# gy1.net
KiCad netlist of a schematic drawn in EAGLE
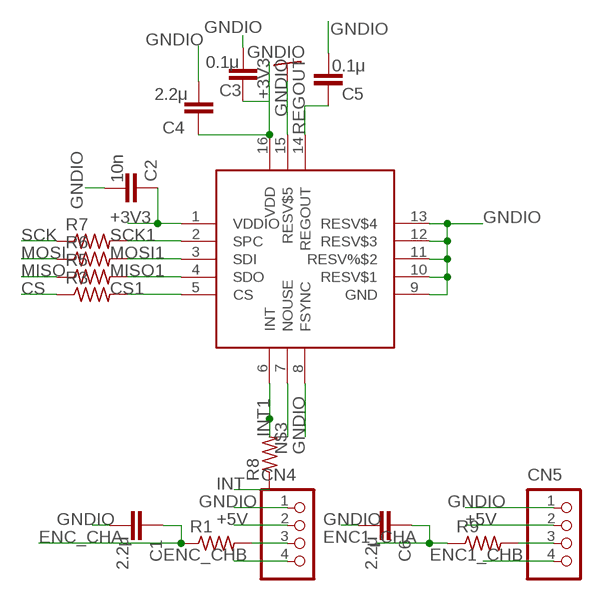
[diagram p0: schematic, sheet 1]
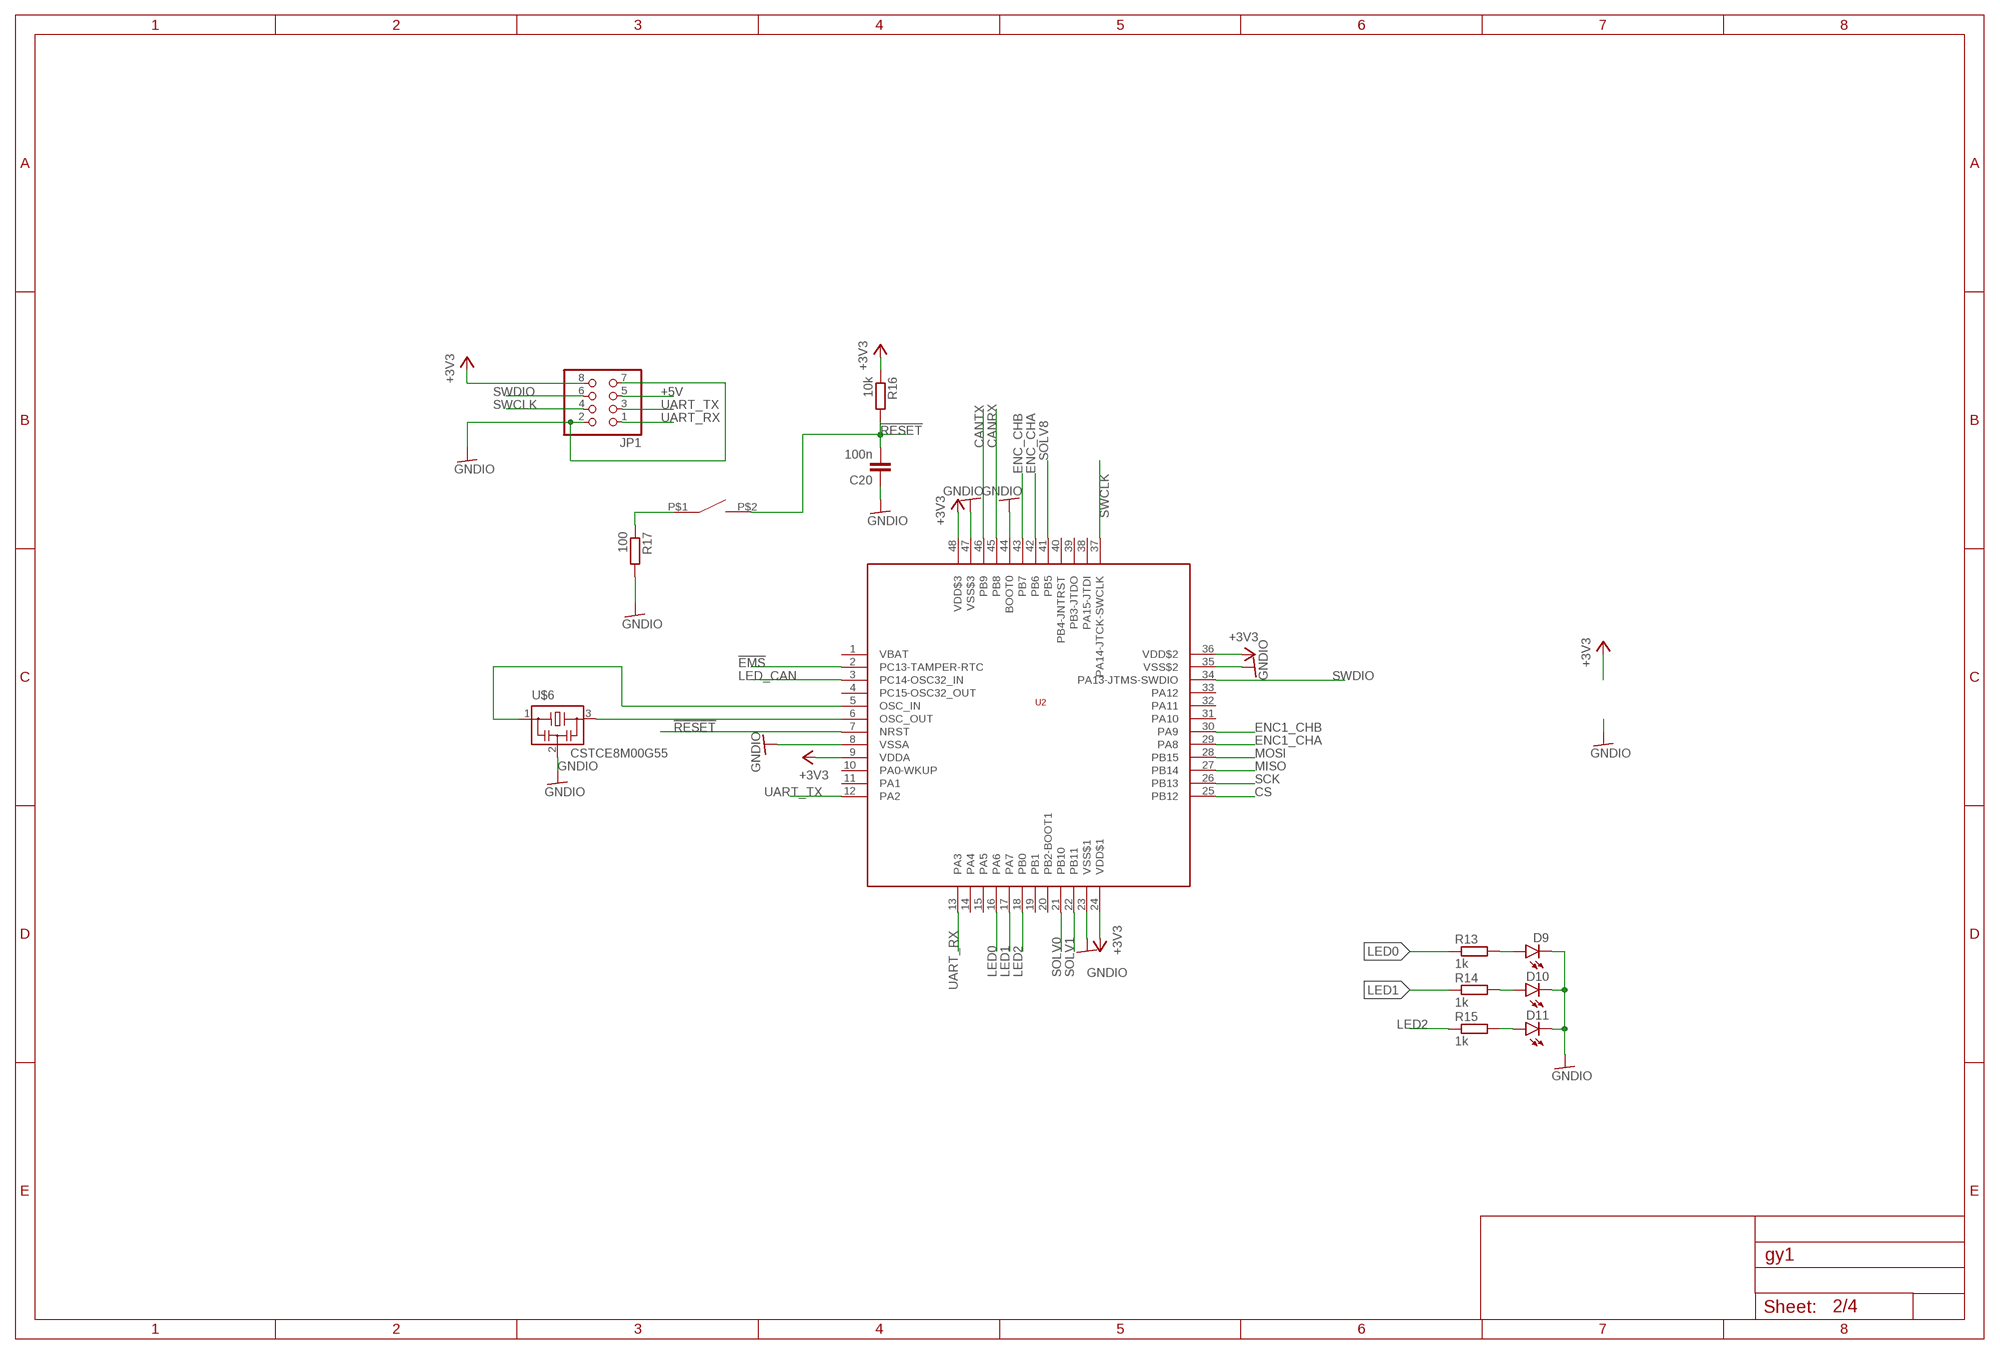
[diagram p1: schematic, sheet 2]
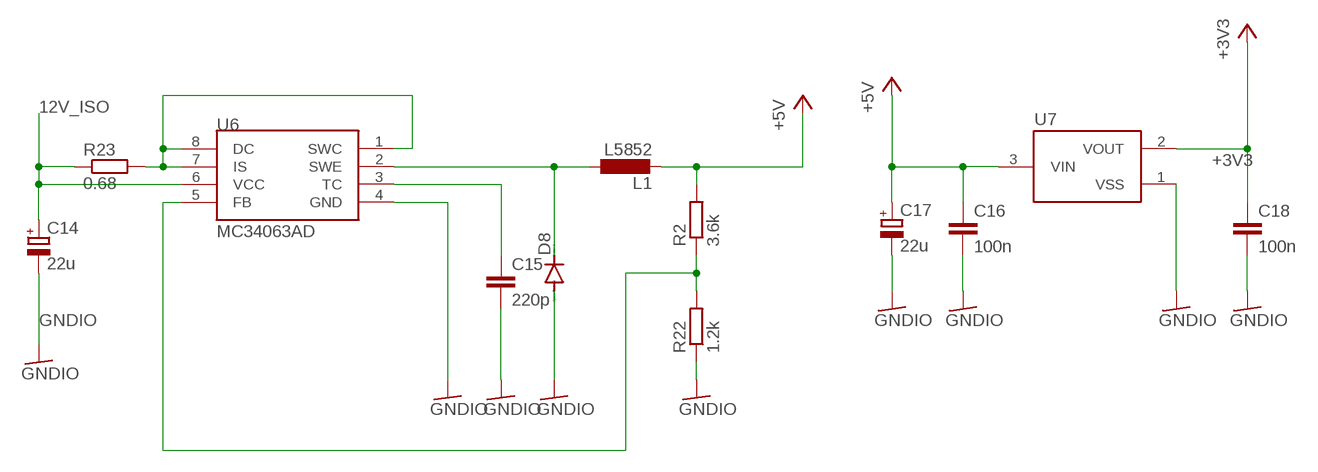
[diagram p2: schematic, sheet 3]
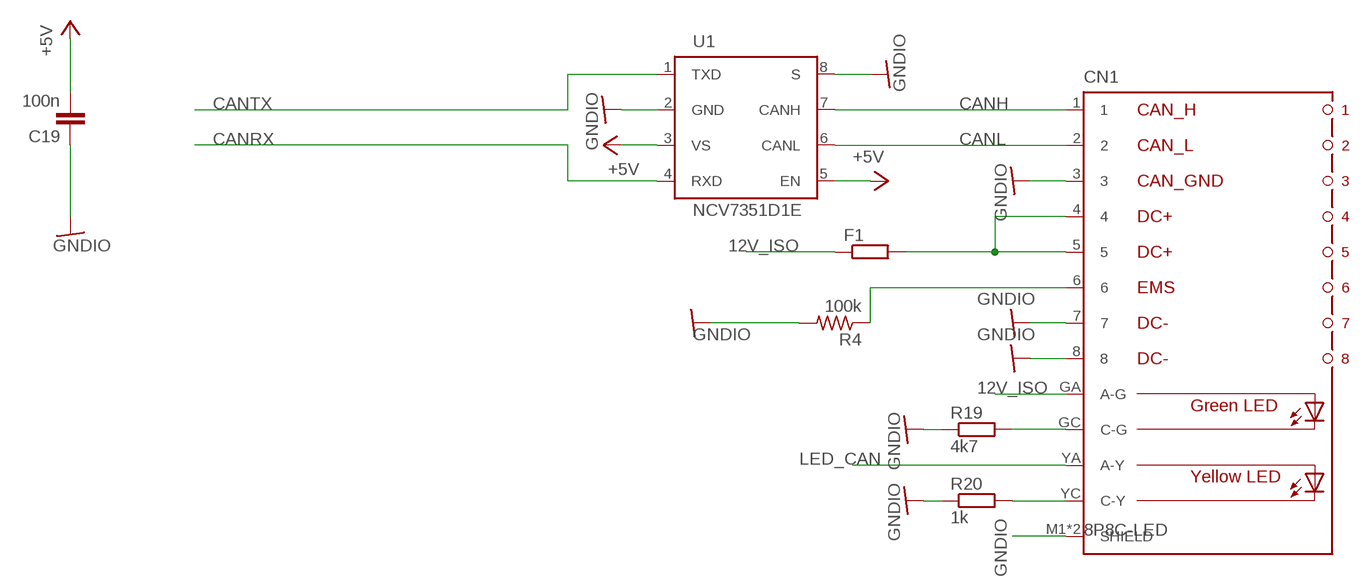
[diagram p3: schematic, sheet 4]

(export (version "E")
  (design (tool "Eeschema 10.0.6"))
  (components
    (comp (ref "C14")
      (value "22u")
      (footprint "eagle-import:E2-5")
      (libsource (lib "eagle-import") (part "CPOL-EUE2-5"))
    )
    (comp (ref "C15")
      (value "220p")
      (footprint "eagle-import:C0603")
      (libsource (lib "eagle-import") (part "rcl_334_C-EUC0603"))
    )
    (comp (ref "C16")
      (value "100n")
      (footprint "eagle-import:C0603")
      (libsource (lib "eagle-import") (part "C-EUC0603"))
    )
    (comp (ref "C17")
      (value "22u")
      (footprint "eagle-import:E2-5")
      (libsource (lib "eagle-import") (part "CPOL-EUE2-5"))
    )
    (comp (ref "C18")
      (value "100n")
      (footprint "eagle-import:C0603")
      (libsource (lib "eagle-import") (part "C-EUC0603"))
    )
    (comp (ref "D8")
      (value "DIODE-SOD123")
      (footprint "eagle-import:SOD123")
      (libsource (lib "eagle-import") (part "DIODE-SOD123"))
    )
    (comp (ref "L1")
      (value "L5852")
      (footprint "eagle-import:L5852")
      (libsource (lib "eagle-import") (part "L5852"))
    )
    (comp (ref "R2")
      (value "3.6k")
      (footprint "eagle-import:R0603")
      (libsource (lib "eagle-import") (part "rcl_334_R-EU_R0603"))
    )
    (comp (ref "R22")
      (value "1.2k")
      (footprint "eagle-import:R0603")
      (libsource (lib "eagle-import") (part "rcl_334_R-EU_R0603"))
    )
    (comp (ref "R23")
      (value "0.68")
      (footprint "eagle-import:R1206")
      (libsource (lib "eagle-import") (part "rcl_334_R-EU_R1206"))
    )
    (comp (ref "U6")
      (value "MC34063AD")
      (footprint "eagle-import:SOIC8")
      (libsource (lib "eagle-import") (part "MC34063AD"))
    )
    (comp (ref "U7")
      (value "XC6206")
      (footprint "eagle-import:SOT95P240X110-3")
      (libsource (lib "eagle-import") (part "XC6206"))
    )
    (comp (ref "C19")
      (value "100n")
      (footprint "eagle-import:C0603")
      (libsource (lib "eagle-import") (part "C-EUC0603"))
    )
    (comp (ref "CN1")
      (value "8P8C-LED")
      (footprint "eagle-import:8P8C-LED")
      (libsource (lib "eagle-import") (part "8P8C-LED"))
    )
    (comp (ref "F1")
      (value "R-EU_R1206")
      (footprint "eagle-import:R1206")
      (libsource (lib "eagle-import") (part "rcl_334_R-EU_R1206"))
    )
    (comp (ref "R4")
      (value "100k")
      (footprint "eagle-import:R0603")
      (libsource (lib "eagle-import") (part "R-US_R0603"))
    )
    (comp (ref "R19")
      (value "4k7")
      (footprint "eagle-import:R0603")
      (libsource (lib "eagle-import") (part "rcl_334_R-EU_R0603"))
    )
    (comp (ref "R20")
      (value "1k")
      (footprint "eagle-import:R0603")
      (libsource (lib "eagle-import") (part "rcl_334_R-EU_R0603"))
    )
    (comp (ref "U1")
      (value "NCV7351D1E")
      (footprint "eagle-import:SO08")
      (libsource (lib "eagle-import") (part "NCV7351D1E"))
    )
    (comp (ref "C20")
      (value "100n")
      (footprint "eagle-import:C0603")
      (libsource (lib "eagle-import") (part "C-EUC0603"))
    )
    (comp (ref "D9")
      (value "LEDCHIPLED_0805")
      (footprint "eagle-import:CHIPLED_0805")
      (libsource (lib "eagle-import") (part "LEDCHIPLED_0805"))
    )
    (comp (ref "D10")
      (value "LEDCHIPLED_0805")
      (footprint "eagle-import:CHIPLED_0805")
      (libsource (lib "eagle-import") (part "LEDCHIPLED_0805"))
    )
    (comp (ref "D11")
      (value "LEDCHIPLED_0805")
      (footprint "eagle-import:CHIPLED_0805")
      (libsource (lib "eagle-import") (part "LEDCHIPLED_0805"))
    )
    (comp (ref "JP1")
      (value "PINHD-2X4")
      (footprint "eagle-import:2X04")
      (libsource (lib "eagle-import") (part "PINHD-2X4"))
    )
    (comp (ref "R13")
      (value "1k")
      (footprint "eagle-import:R0603")
      (libsource (lib "eagle-import") (part "R-EU_R0603"))
    )
    (comp (ref "R14")
      (value "1k")
      (footprint "eagle-import:R0603")
      (libsource (lib "eagle-import") (part "R-EU_R0603"))
    )
    (comp (ref "R15")
      (value "1k")
      (footprint "eagle-import:R0603")
      (libsource (lib "eagle-import") (part "R-EU_R0603"))
    )
    (comp (ref "R16")
      (value "10k")
      (footprint "eagle-import:R0603")
      (libsource (lib "eagle-import") (part "R-EU_R0603"))
    )
    (comp (ref "R17")
      (value "100")
      (footprint "eagle-import:R0603")
      (libsource (lib "eagle-import") (part "R-EU_R0603"))
    )
    (comp (ref "SW1")
      (value "SWITCH_TACTILETOP")
      (footprint "eagle-import:SWITCH_TACTILE_3X6")
      (libsource (lib "eagle-import") (part "SWITCH_TACTILETOP"))
    )
    (comp (ref "U$6")
      (value "CSTCE8M00G55")
      (footprint "eagle-import:CSTCE8M00G55")
      (libsource (lib "eagle-import") (part "CSTCE8M00G55"))
    )
    (comp (ref "U2")
      (value "STM32F103C8")
      (footprint "eagle-import:LQFP48")
      (libsource (lib "eagle-import") (part "STM32F103C8"))
    )
    (comp (ref "C1")
      (value "2.2μ")
      (footprint "eagle-import:C0603")
      (libsource (lib "eagle-import") (part "C-EUC0603"))
    )
    (comp (ref "C2")
      (value "10n")
      (footprint "eagle-import:C0603")
      (libsource (lib "eagle-import") (part "C-EUC0603"))
    )
    (comp (ref "C3")
      (value "0.1μ")
      (footprint "eagle-import:C0603")
      (libsource (lib "eagle-import") (part "C-EUC0603"))
    )
    (comp (ref "C4")
      (value "2.2μ")
      (footprint "eagle-import:C0603")
      (libsource (lib "eagle-import") (part "C-EUC0603"))
    )
    (comp (ref "C5")
      (value "0.1μ")
      (footprint "eagle-import:C0603")
      (libsource (lib "eagle-import") (part "C-EUC0603"))
    )
    (comp (ref "C6")
      (value "2.2μ")
      (footprint "eagle-import:C0603")
      (libsource (lib "eagle-import") (part "C-EUC0603"))
    )
    (comp (ref "CN4")
      (value "S4B-XASK-1")
      (footprint "eagle-import:S4B-XASK-1")
      (libsource (lib "eagle-import") (part "S4B-XASK-1"))
    )
    (comp (ref "CN5")
      (value "S4B-XASK-1")
      (footprint "eagle-import:S4B-XASK-1")
      (libsource (lib "eagle-import") (part "S4B-XASK-1"))
    )
    (comp (ref "R1")
      (value "R-US_R0603")
      (footprint "eagle-import:R0603")
      (libsource (lib "eagle-import") (part "R-US_R0603"))
    )
    (comp (ref "R3")
      (value "R-US_R0603")
      (footprint "eagle-import:R0603")
      (libsource (lib "eagle-import") (part "R-US_R0603"))
    )
    (comp (ref "R5")
      (value "R-US_R0603")
      (footprint "eagle-import:R0603")
      (libsource (lib "eagle-import") (part "R-US_R0603"))
    )
    (comp (ref "R6")
      (value "R-US_R0603")
      (footprint "eagle-import:R0603")
      (libsource (lib "eagle-import") (part "R-US_R0603"))
    )
    (comp (ref "R7")
      (value "R-US_R0603")
      (footprint "eagle-import:R0603")
      (libsource (lib "eagle-import") (part "R-US_R0603"))
    )
    (comp (ref "R8")
      (value "R-US_R0603")
      (footprint "eagle-import:R0603")
      (libsource (lib "eagle-import") (part "R-US_R0603"))
    )
    (comp (ref "R9")
      (value "R-US_R0603")
      (footprint "eagle-import:R0603")
      (libsource (lib "eagle-import") (part "R-US_R0603"))
    )
    (comp (ref "U$1")
      (value "ICM20602")
      (footprint "eagle-import:QFN50P300X300X80-16N")
      (libsource (lib "eagle-import") (part "ICM20602"))
    )
  )
  (nets
    (net (code "1") (name "+3V3") (class "Default")
      (node (ref "C18") (pin "1") (pinfunction "1_1") (pintype "passive"))
      (node (ref "C2") (pin "1") (pinfunction "1_1") (pintype "passive"))
      (node (ref "C3") (pin "1") (pinfunction "1_1") (pintype "passive"))
      (node (ref "C4") (pin "1") (pinfunction "1_1") (pintype "passive"))
      (node (ref "JP1") (pin "8") (pinfunction "8_8") (pintype "passive"))
      (node (ref "R16") (pin "1") (pinfunction "1_1") (pintype "passive"))
      (node (ref "U$1") (pin "1") (pinfunction "VDDIO_1") (pintype "bidirectional"))
      (node (ref "U$1") (pin "16") (pinfunction "VDD_16") (pintype "bidirectional"))
      (node (ref "U2") (pin "24") (pinfunction "VDD$1_24") (pintype "passive"))
      (node (ref "U2") (pin "36") (pinfunction "VDD$2_36") (pintype "passive"))
      (node (ref "U2") (pin "48") (pinfunction "VDD$3_48") (pintype "passive"))
      (node (ref "U2") (pin "9") (pinfunction "VDDA_9") (pintype "bidirectional"))
      (node (ref "U7") (pin "2") (pinfunction "VOUT_2") (pintype "bidirectional"))
    )
    (net (code "2") (name "+5V") (class "Default")
      (node (ref "C16") (pin "1") (pinfunction "1_1") (pintype "passive"))
      (node (ref "C17") (pin "+") (pinfunction "+_+") (pintype "passive"))
      (node (ref "C19") (pin "2") (pinfunction "2_2") (pintype "passive"))
      (node (ref "CN4") (pin "2") (pinfunction "2_2") (pintype "passive"))
      (node (ref "CN5") (pin "2") (pinfunction "2_2") (pintype "passive"))
      (node (ref "JP1") (pin "5") (pinfunction "5_5") (pintype "passive"))
      (node (ref "L1") (pin "P$2") (pinfunction "2_P$2") (pintype "passive"))
      (node (ref "R2") (pin "2") (pinfunction "2_2") (pintype "passive"))
      (node (ref "U1") (pin "3") (pinfunction "VS_3") (pintype "power_in"))
      (node (ref "U1") (pin "5") (pinfunction "EN_5") (pintype "input"))
      (node (ref "U7") (pin "3") (pinfunction "VIN_3") (pintype "bidirectional"))
    )
    (net (code "3") (name "12V_ISO") (class "Default")
      (node (ref "C14") (pin "+") (pinfunction "+_+") (pintype "passive"))
      (node (ref "CN1") (pin "GA") (pinfunction "A-G_GA") (pintype "passive"))
      (node (ref "F1") (pin "1") (pinfunction "1_1") (pintype "passive"))
      (node (ref "R23") (pin "1") (pinfunction "1_1") (pintype "passive"))
      (node (ref "U6") (pin "6") (pinfunction "VCC_6") (pintype "passive"))
    )
    (net (code "4") (name "CANH") (class "Default")
      (node (ref "CN1") (pin "1") (pinfunction "1_1") (pintype "input"))
      (node (ref "U1") (pin "7") (pinfunction "CANH_7") (pintype "output"))
    )
    (net (code "5") (name "CANL") (class "Default")
      (node (ref "CN1") (pin "2") (pinfunction "2_2") (pintype "input"))
      (node (ref "U1") (pin "6") (pinfunction "CANL_6") (pintype "output"))
    )
    (net (code "6") (name "CANRX") (class "Default")
      (node (ref "U1") (pin "4") (pinfunction "RXD_4") (pintype "output"))
      (node (ref "U2") (pin "45") (pinfunction "PB8_45") (pintype "bidirectional"))
    )
    (net (code "7") (name "CANTX") (class "Default")
      (node (ref "U1") (pin "1") (pinfunction "TXD_1") (pintype "input"))
      (node (ref "U2") (pin "46") (pinfunction "PB9_46") (pintype "bidirectional"))
    )
    (net (code "8") (name "CS") (class "Default")
      (node (ref "R3") (pin "1") (pinfunction "1_1") (pintype "passive"))
      (node (ref "U2") (pin "25") (pinfunction "PB12_25") (pintype "bidirectional"))
    )
    (net (code "9") (name "CS1") (class "Default")
      (node (ref "R3") (pin "2") (pinfunction "2_2") (pintype "passive"))
      (node (ref "U$1") (pin "5") (pinfunction "CS_5") (pintype "bidirectional"))
    )
    (net (code "10") (name "ENC1_CHA") (class "Default")
      (node (ref "C6") (pin "1") (pinfunction "1_1") (pintype "passive"))
      (node (ref "R9") (pin "1") (pinfunction "1_1") (pintype "passive"))
      (node (ref "U2") (pin "29") (pinfunction "PA8_29") (pintype "bidirectional"))
    )
    (net (code "11") (name "ENC1_CHB") (class "Default")
      (node (ref "CN5") (pin "4") (pinfunction "4_4") (pintype "passive"))
      (node (ref "U2") (pin "30") (pinfunction "PA9_30") (pintype "bidirectional"))
    )
    (net (code "12") (name "ENC_CHA") (class "Default")
      (node (ref "C1") (pin "1") (pinfunction "1_1") (pintype "passive"))
      (node (ref "R1") (pin "1") (pinfunction "1_1") (pintype "passive"))
      (node (ref "U2") (pin "42") (pinfunction "PB6_42") (pintype "bidirectional"))
    )
    (net (code "13") (name "ENC_CHB") (class "Default")
      (node (ref "CN4") (pin "4") (pinfunction "4_4") (pintype "passive"))
      (node (ref "U2") (pin "43") (pinfunction "PB7_43") (pintype "bidirectional"))
    )
    (net (code "14") (name "GNDIO") (class "Default")
      (node (ref "C1") (pin "2") (pinfunction "2_2") (pintype "passive"))
      (node (ref "C14") (pin "-") (pinfunction "-_-") (pintype "passive"))
      (node (ref "C15") (pin "2") (pinfunction "2_2") (pintype "passive"))
      (node (ref "C16") (pin "2") (pinfunction "2_2") (pintype "passive"))
      (node (ref "C17") (pin "-") (pinfunction "-_-") (pintype "passive"))
      (node (ref "C18") (pin "2") (pinfunction "2_2") (pintype "passive"))
      (node (ref "C19") (pin "1") (pinfunction "1_1") (pintype "passive"))
      (node (ref "C2") (pin "2") (pinfunction "2_2") (pintype "passive"))
      (node (ref "C20") (pin "1") (pinfunction "1_1") (pintype "passive"))
      (node (ref "C3") (pin "2") (pinfunction "2_2") (pintype "passive"))
      (node (ref "C4") (pin "2") (pinfunction "2_2") (pintype "passive"))
      (node (ref "C5") (pin "2") (pinfunction "2_2") (pintype "passive"))
      (node (ref "C6") (pin "2") (pinfunction "2_2") (pintype "passive"))
      (node (ref "CN1") (pin "3") (pinfunction "3_3") (pintype "input"))
      (node (ref "CN1") (pin "7") (pinfunction "7_7") (pintype "input"))
      (node (ref "CN1") (pin "8") (pinfunction "8_8") (pintype "input"))
      (node (ref "CN1") (pin "M1") (pinfunction "SHIELD_M1") (pintype "passive"))
      (node (ref "CN1") (pin "M2") (pinfunction "SHIELD_M2") (pintype "passive"))
      (node (ref "CN4") (pin "1") (pinfunction "1_1") (pintype "passive"))
      (node (ref "CN5") (pin "1") (pinfunction "1_1") (pintype "passive"))
      (node (ref "D10") (pin "C") (pinfunction "C_C") (pintype "passive"))
      (node (ref "D11") (pin "C") (pinfunction "C_C") (pintype "passive"))
      (node (ref "D8") (pin "A") (pinfunction "A_A") (pintype "passive"))
      (node (ref "D9") (pin "C") (pinfunction "C_C") (pintype "passive"))
      (node (ref "JP1") (pin "2") (pinfunction "2_2") (pintype "passive"))
      (node (ref "JP1") (pin "7") (pinfunction "7_7") (pintype "passive"))
      (node (ref "R17") (pin "2") (pinfunction "2_2") (pintype "passive"))
      (node (ref "R19") (pin "1") (pinfunction "1_1") (pintype "passive"))
      (node (ref "R20") (pin "1") (pinfunction "1_1") (pintype "passive"))
      (node (ref "R22") (pin "1") (pinfunction "1_1") (pintype "passive"))
      (node (ref "R4") (pin "2") (pinfunction "2_2") (pintype "passive"))
      (node (ref "U$1") (pin "10") (pinfunction "RESV$1_10") (pintype "bidirectional"))
      (node (ref "U$1") (pin "11") (pinfunction "RESV%$2_11") (pintype "bidirectional"))
      (node (ref "U$1") (pin "12") (pinfunction "RESV$3_12") (pintype "bidirectional"))
      (node (ref "U$1") (pin "13") (pinfunction "RESV$4_13") (pintype "bidirectional"))
      (node (ref "U$1") (pin "15") (pinfunction "RESV$5_15") (pintype "bidirectional"))
      (node (ref "U$1") (pin "8") (pinfunction "FSYNC_8") (pintype "bidirectional"))
      (node (ref "U$1") (pin "9") (pinfunction "GND_9") (pintype "bidirectional"))
      (node (ref "U$6") (pin "2") (pinfunction "2_2") (pintype "passive"))
      (node (ref "U1") (pin "2") (pinfunction "GND_2") (pintype "power_in"))
      (node (ref "U1") (pin "8") (pinfunction "S_8") (pintype "input"))
      (node (ref "U2") (pin "23") (pinfunction "VSS$1_23") (pintype "passive"))
      (node (ref "U2") (pin "35") (pinfunction "VSS$2_35") (pintype "passive"))
      (node (ref "U2") (pin "44") (pinfunction "BOOT0_44") (pintype "input"))
      (node (ref "U2") (pin "47") (pinfunction "VSS$3_47") (pintype "passive"))
      (node (ref "U2") (pin "8") (pinfunction "VSSA_8") (pintype "bidirectional"))
      (node (ref "U6") (pin "4") (pinfunction "GND_4") (pintype "passive"))
      (node (ref "U7") (pin "1") (pinfunction "VSS_1") (pintype "bidirectional"))
    )
    (net (code "15") (name "INT") (class "Default")
      (node (ref "R8") (pin "1") (pinfunction "1_1") (pintype "passive"))
    )
    (net (code "16") (name "INT1") (class "Default")
      (node (ref "R8") (pin "2") (pinfunction "2_2") (pintype "passive"))
      (node (ref "U$1") (pin "6") (pinfunction "INT_6") (pintype "bidirectional"))
    )
    (net (code "17") (name "LED0") (class "Default")
      (node (ref "R13") (pin "1") (pinfunction "1_1") (pintype "passive"))
      (node (ref "U2") (pin "16") (pinfunction "PA6_16") (pintype "bidirectional"))
    )
    (net (code "18") (name "LED1") (class "Default")
      (node (ref "R14") (pin "1") (pinfunction "1_1") (pintype "passive"))
      (node (ref "U2") (pin "17") (pinfunction "PA7_17") (pintype "bidirectional"))
    )
    (net (code "19") (name "LED2") (class "Default")
      (node (ref "R15") (pin "1") (pinfunction "1_1") (pintype "passive"))
      (node (ref "U2") (pin "18") (pinfunction "PB0_18") (pintype "bidirectional"))
    )
    (net (code "20") (name "LED_CAN") (class "Default")
      (node (ref "CN1") (pin "YA") (pinfunction "A-Y_YA") (pintype "passive"))
      (node (ref "U2") (pin "3") (pinfunction "PC14-OSC32_IN_3") (pintype "bidirectional"))
    )
    (net (code "21") (name "MISO") (class "Default")
      (node (ref "R5") (pin "1") (pinfunction "1_1") (pintype "passive"))
      (node (ref "U2") (pin "27") (pinfunction "PB14_27") (pintype "bidirectional"))
    )
    (net (code "22") (name "MISO1") (class "Default")
      (node (ref "R5") (pin "2") (pinfunction "2_2") (pintype "passive"))
      (node (ref "U$1") (pin "4") (pinfunction "SDO_4") (pintype "bidirectional"))
    )
    (net (code "23") (name "MOSI") (class "Default")
      (node (ref "R6") (pin "1") (pinfunction "1_1") (pintype "passive"))
      (node (ref "U2") (pin "28") (pinfunction "PB15_28") (pintype "bidirectional"))
    )
    (net (code "24") (name "MOSI1") (class "Default")
      (node (ref "R6") (pin "2") (pinfunction "2_2") (pintype "passive"))
      (node (ref "U$1") (pin "3") (pinfunction "SDI_3") (pintype "bidirectional"))
    )
    (net (code "25") (name "N$3") (class "Default")
      (node (ref "U$1") (pin "7") (pinfunction "NOUSE_7") (pintype "bidirectional"))
    )
    (net (code "26") (name "Net-(CN1-C-G)") (class "Default")
      (node (ref "CN1") (pin "GC") (pinfunction "C-G_GC") (pintype "passive"))
      (node (ref "R19") (pin "2") (pinfunction "2_2") (pintype "passive"))
    )
    (net (code "27") (name "Net-(CN1-C-Y)") (class "Default")
      (node (ref "CN1") (pin "YC") (pinfunction "C-Y_YC") (pintype "passive"))
      (node (ref "R20") (pin "2") (pinfunction "2_2") (pintype "passive"))
    )
    (net (code "28") (name "Net-(CN1-Pad4)") (class "Default")
      (node (ref "CN1") (pin "4") (pinfunction "4_4") (pintype "input"))
      (node (ref "CN1") (pin "5") (pinfunction "5_5") (pintype "input"))
      (node (ref "F1") (pin "2") (pinfunction "2_2") (pintype "passive"))
    )
    (net (code "29") (name "Net-(CN1-Pad6)") (class "Default")
      (node (ref "CN1") (pin "6") (pinfunction "6_6") (pintype "input"))
      (node (ref "R4") (pin "1") (pinfunction "1_1") (pintype "passive"))
    )
    (net (code "30") (name "Net-(CN4-Pad3)") (class "Default")
      (node (ref "CN4") (pin "3") (pinfunction "3_3") (pintype "passive"))
      (node (ref "R1") (pin "2") (pinfunction "2_2") (pintype "passive"))
    )
    (net (code "31") (name "Net-(CN5-Pad3)") (class "Default")
      (node (ref "CN5") (pin "3") (pinfunction "3_3") (pintype "passive"))
      (node (ref "R9") (pin "2") (pinfunction "2_2") (pintype "passive"))
    )
    (net (code "32") (name "Net-(D9-PadA)") (class "Default")
      (node (ref "D9") (pin "A") (pinfunction "A_A") (pintype "passive"))
      (node (ref "R13") (pin "2") (pinfunction "2_2") (pintype "passive"))
    )
    (net (code "33") (name "Net-(D10-PadA)") (class "Default")
      (node (ref "D10") (pin "A") (pinfunction "A_A") (pintype "passive"))
      (node (ref "R14") (pin "2") (pinfunction "2_2") (pintype "passive"))
    )
    (net (code "34") (name "Net-(D11-PadA)") (class "Default")
      (node (ref "D11") (pin "A") (pinfunction "A_A") (pintype "passive"))
      (node (ref "R15") (pin "2") (pinfunction "2_2") (pintype "passive"))
    )
    (net (code "35") (name "Net-(L1-1)") (class "Default")
      (node (ref "D8") (pin "C") (pinfunction "C_C") (pintype "passive"))
      (node (ref "L1") (pin "P$1") (pinfunction "1_P$1") (pintype "passive"))
      (node (ref "U6") (pin "2") (pinfunction "SWE_2") (pintype "passive"))
    )
    (net (code "36") (name "Net-(SW1-1)") (class "Default")
      (node (ref "R17") (pin "1") (pinfunction "1_1") (pintype "passive"))
      (node (ref "SW1") (pin "P$1") (pinfunction "1_P$1") (pintype "bidirectional"))
    )
    (net (code "37") (name "Net-(U2-OSC_IN)") (class "Default")
      (node (ref "U$6") (pin "1") (pinfunction "1_1") (pintype "passive"))
      (node (ref "U2") (pin "5") (pinfunction "OSC_IN_5") (pintype "input"))
    )
    (net (code "38") (name "Net-(U2-OSC_OUT)") (class "Default")
      (node (ref "U$6") (pin "3") (pinfunction "3_3") (pintype "passive"))
      (node (ref "U2") (pin "6") (pinfunction "OSC_OUT_6") (pintype "output"))
    )
    (net (code "39") (name "Net-(U6-DC)") (class "Default")
      (node (ref "R23") (pin "2") (pinfunction "2_2") (pintype "passive"))
      (node (ref "U6") (pin "1") (pinfunction "SWC_1") (pintype "passive"))
      (node (ref "U6") (pin "7") (pinfunction "IS_7") (pintype "passive"))
      (node (ref "U6") (pin "8") (pinfunction "DC_8") (pintype "passive"))
    )
    (net (code "40") (name "Net-(U6-FB)") (class "Default")
      (node (ref "R2") (pin "1") (pinfunction "1_1") (pintype "passive"))
      (node (ref "R22") (pin "2") (pinfunction "2_2") (pintype "passive"))
      (node (ref "U6") (pin "5") (pinfunction "FB_5") (pintype "passive"))
    )
    (net (code "41") (name "Net-(U6-TC)") (class "Default")
      (node (ref "C15") (pin "1") (pinfunction "1_1") (pintype "passive"))
      (node (ref "U6") (pin "3") (pinfunction "TC_3") (pintype "passive"))
    )
    (net (code "42") (name "REGOUT") (class "Default")
      (node (ref "C5") (pin "1") (pinfunction "1_1") (pintype "passive"))
      (node (ref "U$1") (pin "14") (pinfunction "REGOUT_14") (pintype "bidirectional"))
    )
    (net (code "43") (name "SCK") (class "Default")
      (node (ref "R7") (pin "1") (pinfunction "1_1") (pintype "passive"))
      (node (ref "U2") (pin "26") (pinfunction "PB13_26") (pintype "bidirectional"))
    )
    (net (code "44") (name "SCK1") (class "Default")
      (node (ref "R7") (pin "2") (pinfunction "2_2") (pintype "passive"))
      (node (ref "U$1") (pin "2") (pinfunction "SPC_2") (pintype "bidirectional"))
    )
    (net (code "45") (name "SOLV0") (class "Default")
      (node (ref "U2") (pin "21") (pinfunction "PB10_21") (pintype "bidirectional"))
    )
    (net (code "46") (name "SOLV1") (class "Default")
      (node (ref "U2") (pin "22") (pinfunction "PB11_22") (pintype "bidirectional"))
    )
    (net (code "47") (name "SOLV8") (class "Default")
      (node (ref "U2") (pin "41") (pinfunction "PB5_41") (pintype "bidirectional"))
    )
    (net (code "48") (name "SWCLK") (class "Default")
      (node (ref "JP1") (pin "4") (pinfunction "4_4") (pintype "passive"))
      (node (ref "U2") (pin "37") (pinfunction "PA14-JTCK-SWCLK_37") (pintype "bidirectional"))
    )
    (net (code "49") (name "SWDIO") (class "Default")
      (node (ref "JP1") (pin "6") (pinfunction "6_6") (pintype "passive"))
      (node (ref "U2") (pin "34") (pinfunction "PA13-JTMS-SWDIO_34") (pintype "bidirectional"))
    )
    (net (code "50") (name "UART_RX") (class "Default")
      (node (ref "JP1") (pin "1") (pinfunction "1_1") (pintype "passive"))
      (node (ref "U2") (pin "13") (pinfunction "PA3_13") (pintype "bidirectional"))
    )
    (net (code "51") (name "UART_TX") (class "Default")
      (node (ref "JP1") (pin "3") (pinfunction "3_3") (pintype "passive"))
      (node (ref "U2") (pin "12") (pinfunction "PA2_12") (pintype "bidirectional"))
    )
    (net (code "52") (name "unconnected-(U2-PA0-WKUP-Pad10)") (class "Default")
      (node (ref "U2") (pin "10") (pinfunction "PA0-WKUP_10") (pintype "bidirectional"))
    )
    (net (code "53") (name "unconnected-(U2-PA1-Pad11)") (class "Default")
      (node (ref "U2") (pin "11") (pinfunction "PA1_11") (pintype "bidirectional"))
    )
    (net (code "54") (name "unconnected-(U2-PA4-Pad14)") (class "Default")
      (node (ref "U2") (pin "14") (pinfunction "PA4_14") (pintype "bidirectional"))
    )
    (net (code "55") (name "unconnected-(U2-PA5-Pad15)") (class "Default")
      (node (ref "U2") (pin "15") (pinfunction "PA5_15") (pintype "bidirectional"))
    )
    (net (code "56") (name "unconnected-(U2-PA10-Pad31)") (class "Default")
      (node (ref "U2") (pin "31") (pinfunction "PA10_31") (pintype "bidirectional"))
    )
    (net (code "57") (name "unconnected-(U2-PA11-Pad32)") (class "Default")
      (node (ref "U2") (pin "32") (pinfunction "PA11_32") (pintype "bidirectional"))
    )
    (net (code "58") (name "unconnected-(U2-PA12-Pad33)") (class "Default")
      (node (ref "U2") (pin "33") (pinfunction "PA12_33") (pintype "bidirectional"))
    )
    (net (code "59") (name "unconnected-(U2-PA15-JTDI-Pad38)") (class "Default")
      (node (ref "U2") (pin "38") (pinfunction "PA15-JTDI_38") (pintype "bidirectional"))
    )
    (net (code "60") (name "unconnected-(U2-PB1-Pad19)") (class "Default")
      (node (ref "U2") (pin "19") (pinfunction "PB1_19") (pintype "bidirectional"))
    )
    (net (code "61") (name "unconnected-(U2-PB2-BOOT1-Pad20)") (class "Default")
      (node (ref "U2") (pin "20") (pinfunction "PB2-BOOT1_20") (pintype "bidirectional"))
    )
    (net (code "62") (name "unconnected-(U2-PB3-JTDO-Pad39)") (class "Default")
      (node (ref "U2") (pin "39") (pinfunction "PB3-JTDO_39") (pintype "bidirectional"))
    )
    (net (code "63") (name "unconnected-(U2-PB4-JNTRST-Pad40)") (class "Default")
      (node (ref "U2") (pin "40") (pinfunction "PB4-JNTRST_40") (pintype "bidirectional"))
    )
    (net (code "64") (name "unconnected-(U2-PC15-OSC32_OUT-Pad4)") (class "Default")
      (node (ref "U2") (pin "4") (pinfunction "PC15-OSC32_OUT_4") (pintype "bidirectional"))
    )
    (net (code "65") (name "unconnected-(U2-VBAT-Pad1)") (class "Default")
      (node (ref "U2") (pin "1") (pinfunction "VBAT_1") (pintype "passive"))
    )
    (net (code "66") (name "~{EMS}") (class "Default")
      (node (ref "U2") (pin "2") (pinfunction "PC13-TAMPER-RTC_2") (pintype "bidirectional"))
    )
    (net (code "67") (name "~{RESET}") (class "Default")
      (node (ref "C20") (pin "2") (pinfunction "2_2") (pintype "passive"))
      (node (ref "R16") (pin "2") (pinfunction "2_2") (pintype "passive"))
      (node (ref "SW1") (pin "P$2") (pinfunction "2_P$2") (pintype "bidirectional"))
      (node (ref "U2") (pin "7") (pinfunction "NRST_7") (pintype "bidirectional"))
    )
  )
)
